# schematic.net
KiCad netlist of a schematic drawn in EasyEDA
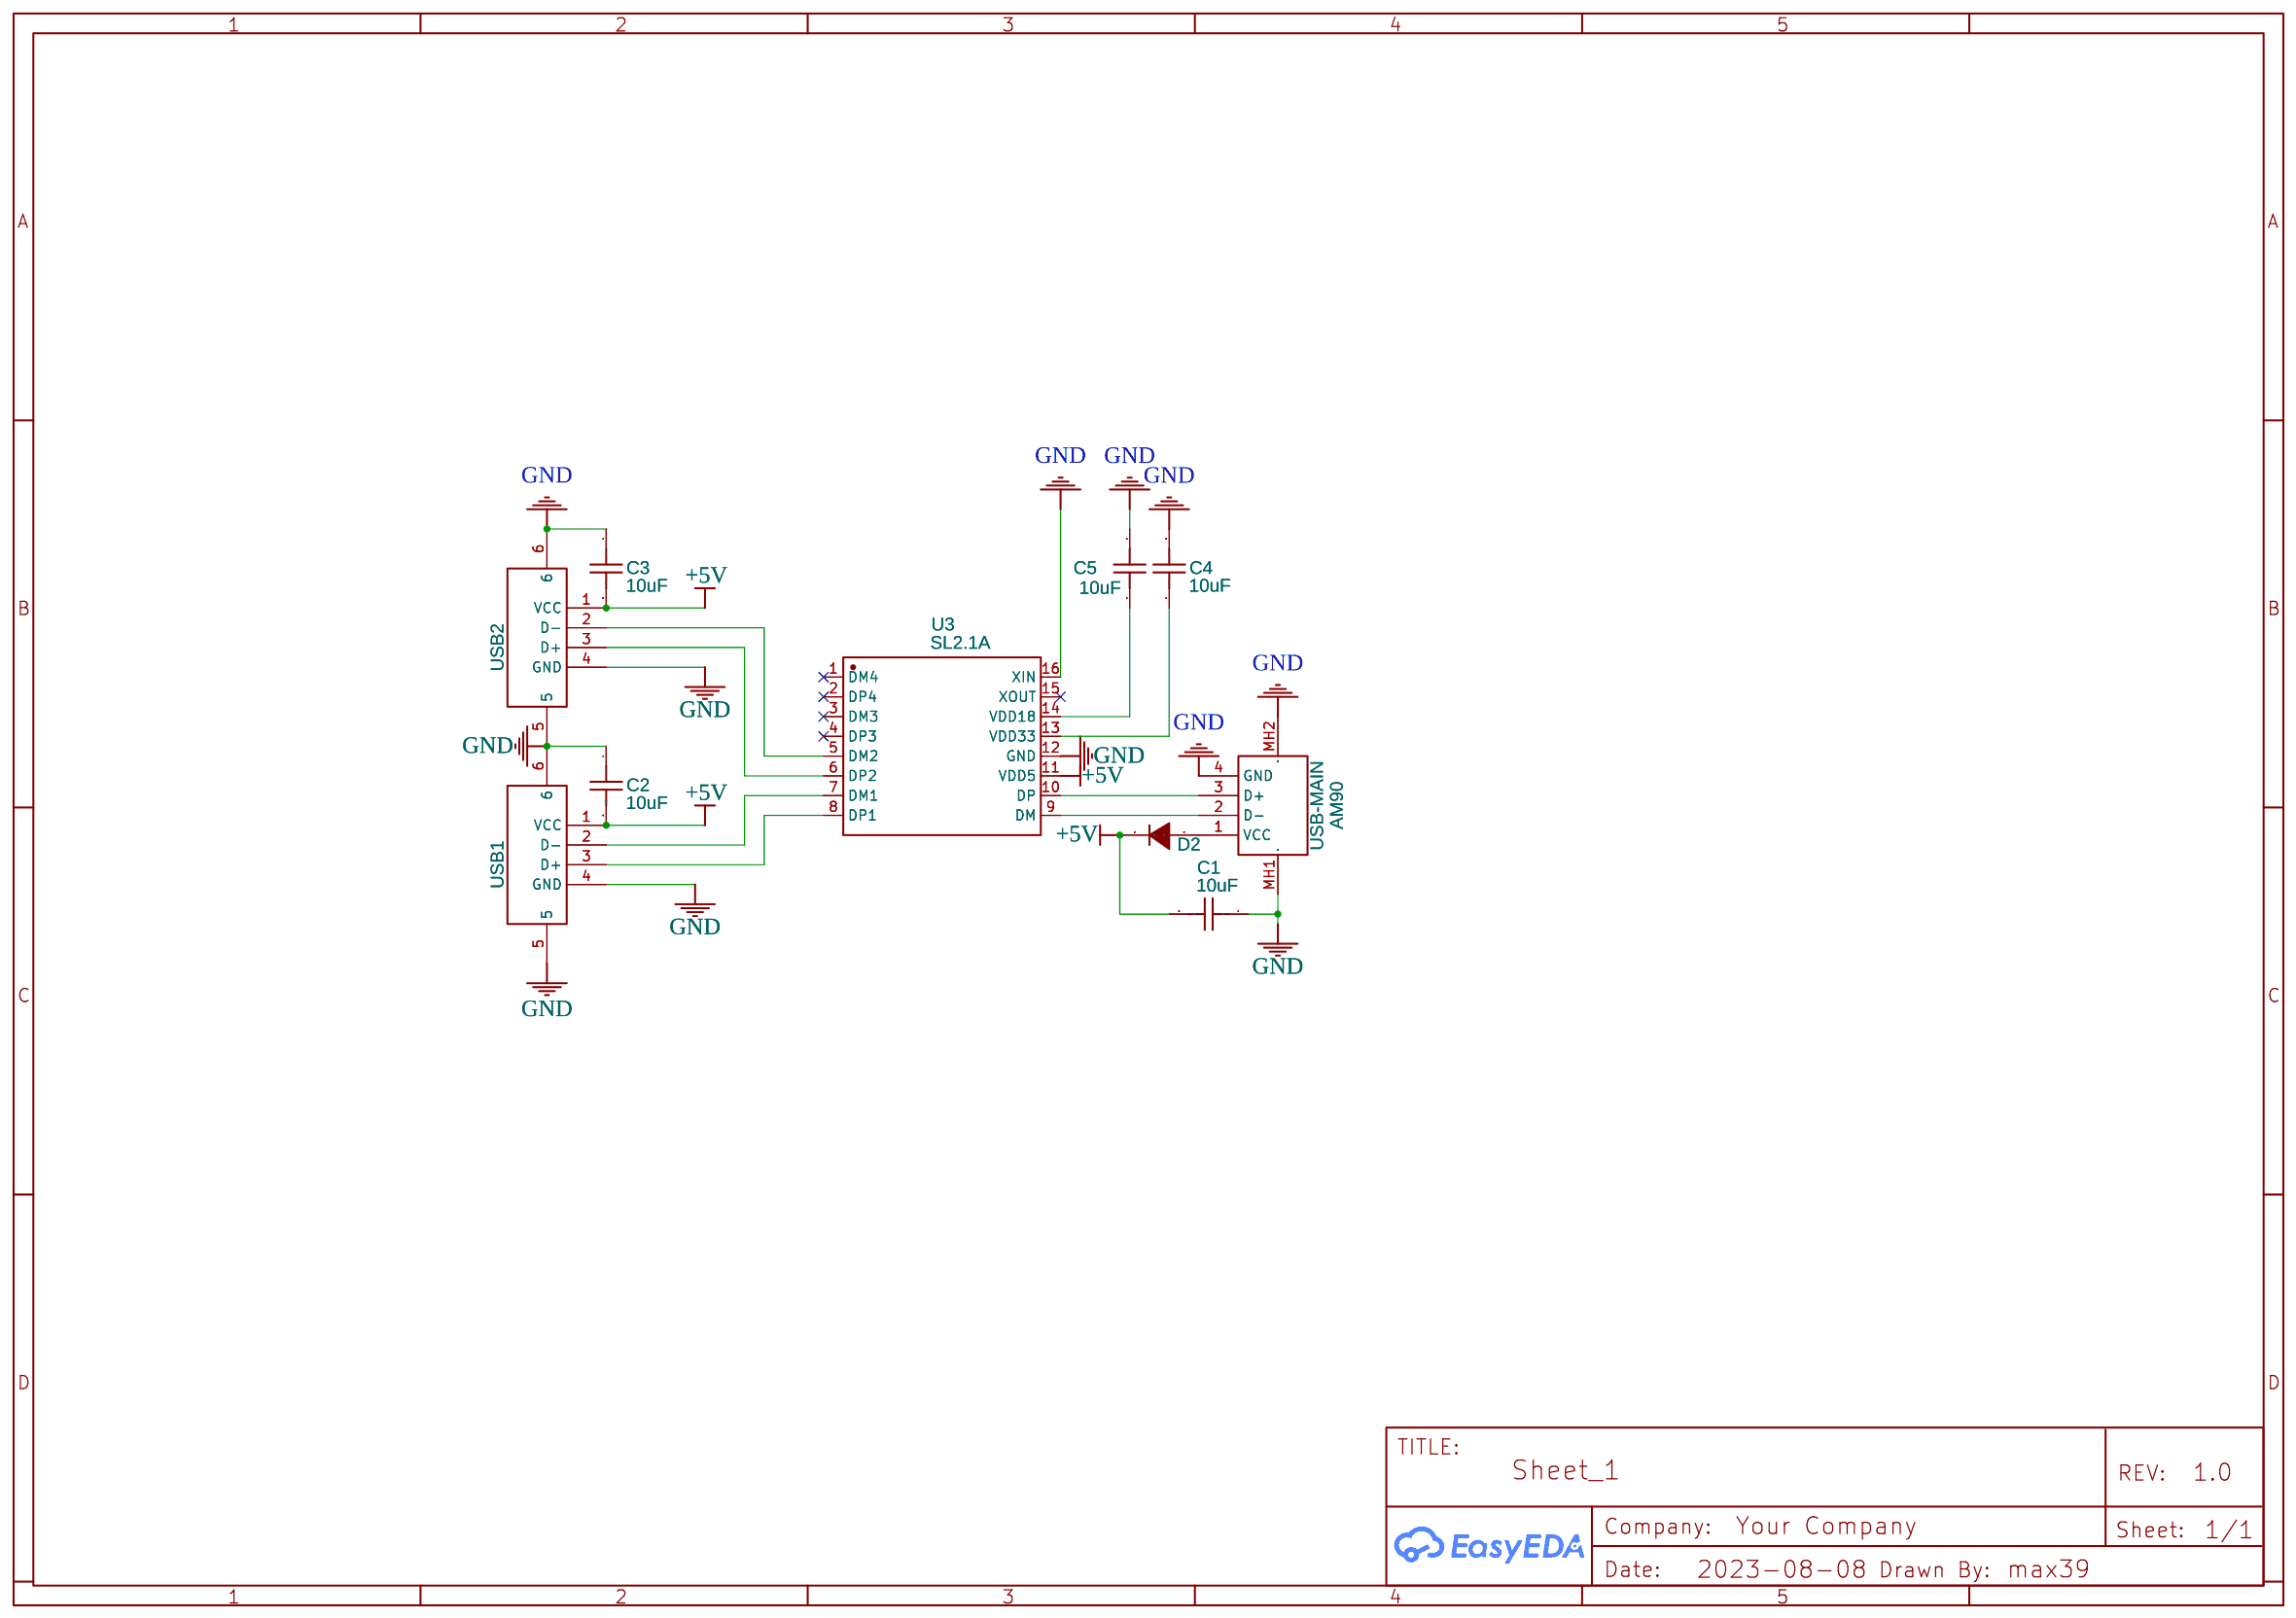
[diagram p0: schematic sheet]

(export (version "E")
  (design (tool "Eeschema 10.0.6"))
  (components
    (comp (ref "C1")
      (value "10uF")
      (fields
        (field (name "Manufacturer Part") "CL10A106KP8NNNC")
        (field (name "Manufacturer") "SAMSUNG(三星)")
      )
      (libsource (lib "") (part "CL10A106KP8NNNC"))
    )
    (comp (ref "C2")
      (value "10uF")
      (fields
        (field (name "Manufacturer Part") "CL10A106KP8NNNC")
        (field (name "Manufacturer") "SAMSUNG(三星)")
      )
      (libsource (lib "") (part "CL10A106KP8NNNC_1"))
    )
    (comp (ref "C3")
      (value "10uF")
      (fields
        (field (name "Manufacturer Part") "CL10A106KP8NNNC")
        (field (name "Manufacturer") "SAMSUNG(三星)")
      )
      (libsource (lib "") (part "CL10A106KP8NNNC_1"))
    )
    (comp (ref "C4") (value "10uF") (libsource (lib "") (part "C_0603_US")))
    (comp (ref "C5") (value "10uF") (libsource (lib "") (part "C_0603_US")))
    (comp (ref "D2")
      (value "NSR0320MW2T1G")
      (fields (field (name "Manufacturer") "onsemi(安森美)"))
      (libsource (lib "") (part "NSR0320MW2T1G"))
    )
    (comp (ref "U3")
      (value "SL2.1A")
      (fields (field (name "Manufacturer") "CoreChips(和芯润德)"))
      (libsource (lib "") (part "SL2.1A"))
    )
    (comp (ref "USB-MAIN")
      (value "AM90")
      (fields (field (name "Manufacturer") "SHOU HAN(首韩)"))
      (libsource (lib "") (part "AM90"))
    )
    (comp (ref "USB1")
      (value "USB-AF-90-14.4X13.6-H7.0-DIP")
      (fields (field (name "Manufacturer Part") "903-131A1011D10100") (field (name "Manufacturer") "精拓金"))
      (libsource (lib "") (part "USB-AF-90-14.4X13.6-H7.0-DIP"))
    )
    (comp (ref "USB2")
      (value "USB-AF-90-14.4X13.6-H7.0-DIP")
      (fields (field (name "Manufacturer Part") "903-131A1011D10100") (field (name "Manufacturer") "精拓金"))
      (libsource (lib "") (part "USB-AF-90-14.4X13.6-H7.0-DIP"))
    )
  )
  (nets
    (net (code "1") (name "+5V") (class "Default")
      (node (ref "C1") (pin "2") (pinfunction "2_2") (pintype "unspecified"))
      (node (ref "C2") (pin "2") (pinfunction "2_2") (pintype "unspecified"))
      (node (ref "C3") (pin "2") (pinfunction "2_2") (pintype "unspecified"))
      (node (ref "D2") (pin "1") (pinfunction "C_1") (pintype "unspecified"))
      (node (ref "U3") (pin "11") (pinfunction "VDD5_11") (pintype "unspecified"))
      (node (ref "USB1") (pin "1") (pinfunction "VCC_1") (pintype "unspecified"))
      (node (ref "USB2") (pin "1") (pinfunction "VCC_1") (pintype "unspecified"))
    )
    (net (code "2") (name "GND") (class "Default")
      (node (ref "C1") (pin "1") (pinfunction "1_1") (pintype "unspecified"))
      (node (ref "C2") (pin "1") (pinfunction "1_1") (pintype "unspecified"))
      (node (ref "C3") (pin "1") (pinfunction "1_1") (pintype "unspecified"))
      (node (ref "C4") (pin "2") (pinfunction "2_2") (pintype "unspecified"))
      (node (ref "C5") (pin "2") (pinfunction "2_2") (pintype "unspecified"))
      (node (ref "U3") (pin "12") (pinfunction "GND_12") (pintype "unspecified"))
      (node (ref "U3") (pin "16") (pinfunction "XIN_16") (pintype "unspecified"))
      (node (ref "USB-MAIN") (pin "4") (pinfunction "GND_4") (pintype "input"))
      (node (ref "USB-MAIN") (pin "MH1") (pinfunction "MH1_MH1") (pintype "unspecified"))
      (node (ref "USB-MAIN") (pin "MH2") (pinfunction "MH2_MH2") (pintype "unspecified"))
      (node (ref "USB1") (pin "4") (pinfunction "GND_4") (pintype "unspecified"))
      (node (ref "USB1") (pin "5") (pinfunction "5_5") (pintype "unspecified"))
      (node (ref "USB1") (pin "6") (pinfunction "6_6") (pintype "unspecified"))
      (node (ref "USB2") (pin "4") (pinfunction "GND_4") (pintype "unspecified"))
      (node (ref "USB2") (pin "5") (pinfunction "5_5") (pintype "unspecified"))
      (node (ref "USB2") (pin "6") (pinfunction "6_6") (pintype "unspecified"))
    )
    (net (code "3") (name "Net-(D2-A)") (class "Default")
      (node (ref "D2") (pin "2") (pinfunction "A_2") (pintype "unspecified"))
      (node (ref "USB-MAIN") (pin "1") (pinfunction "VCC_1") (pintype "input"))
    )
    (net (code "4") (name "Net-(U3-DM)") (class "Default")
      (node (ref "U3") (pin "9") (pinfunction "DM_9") (pintype "unspecified"))
      (node (ref "USB-MAIN") (pin "2") (pinfunction "D-_2") (pintype "input"))
    )
    (net (code "5") (name "Net-(U3-DM1)") (class "Default")
      (node (ref "U3") (pin "7") (pinfunction "DM1_7") (pintype "unspecified"))
      (node (ref "USB1") (pin "2") (pinfunction "D-_2") (pintype "unspecified"))
    )
    (net (code "6") (name "Net-(U3-DM2)") (class "Default")
      (node (ref "U3") (pin "5") (pinfunction "DM2_5") (pintype "unspecified"))
      (node (ref "USB2") (pin "2") (pinfunction "D-_2") (pintype "unspecified"))
    )
    (net (code "7") (name "Net-(U3-DP)") (class "Default")
      (node (ref "U3") (pin "10") (pinfunction "DP_10") (pintype "unspecified"))
      (node (ref "USB-MAIN") (pin "3") (pinfunction "D+_3") (pintype "input"))
    )
    (net (code "8") (name "Net-(U3-DP1)") (class "Default")
      (node (ref "U3") (pin "8") (pinfunction "DP1_8") (pintype "unspecified"))
      (node (ref "USB1") (pin "3") (pinfunction "D+_3") (pintype "unspecified"))
    )
    (net (code "9") (name "Net-(U3-DP2)") (class "Default")
      (node (ref "U3") (pin "6") (pinfunction "DP2_6") (pintype "unspecified"))
      (node (ref "USB2") (pin "3") (pinfunction "D+_3") (pintype "unspecified"))
    )
    (net (code "10") (name "Net-(U3-VDD18)") (class "Default")
      (node (ref "C5") (pin "1") (pinfunction "1_1") (pintype "unspecified"))
      (node (ref "U3") (pin "14") (pinfunction "VDD18_14") (pintype "unspecified"))
    )
    (net (code "11") (name "Net-(U3-VDD33)") (class "Default")
      (node (ref "C4") (pin "1") (pinfunction "1_1") (pintype "unspecified"))
      (node (ref "U3") (pin "13") (pinfunction "VDD33_13") (pintype "unspecified"))
    )
    (net (code "12") (name "unconnected-(U3-DM3-Pad3)") (class "Default")
      (node (ref "U3") (pin "3") (pinfunction "DM3_3") (pintype "unspecified+no_connect"))
    )
    (net (code "13") (name "unconnected-(U3-DM4-Pad1)") (class "Default")
      (node (ref "U3") (pin "1") (pinfunction "DM4_1") (pintype "unspecified+no_connect"))
    )
    (net (code "14") (name "unconnected-(U3-DP3-Pad4)") (class "Default")
      (node (ref "U3") (pin "4") (pinfunction "DP3_4") (pintype "unspecified+no_connect"))
    )
    (net (code "15") (name "unconnected-(U3-DP4-Pad2)") (class "Default")
      (node (ref "U3") (pin "2") (pinfunction "DP4_2") (pintype "unspecified+no_connect"))
    )
    (net (code "16") (name "unconnected-(U3-XOUT-Pad15)") (class "Default")
      (node (ref "U3") (pin "15") (pinfunction "XOUT_15") (pintype "unspecified+no_connect"))
    )
  )
)
